# 1_4.net
KiCad netlist of a schematic drawn in Altium Designer
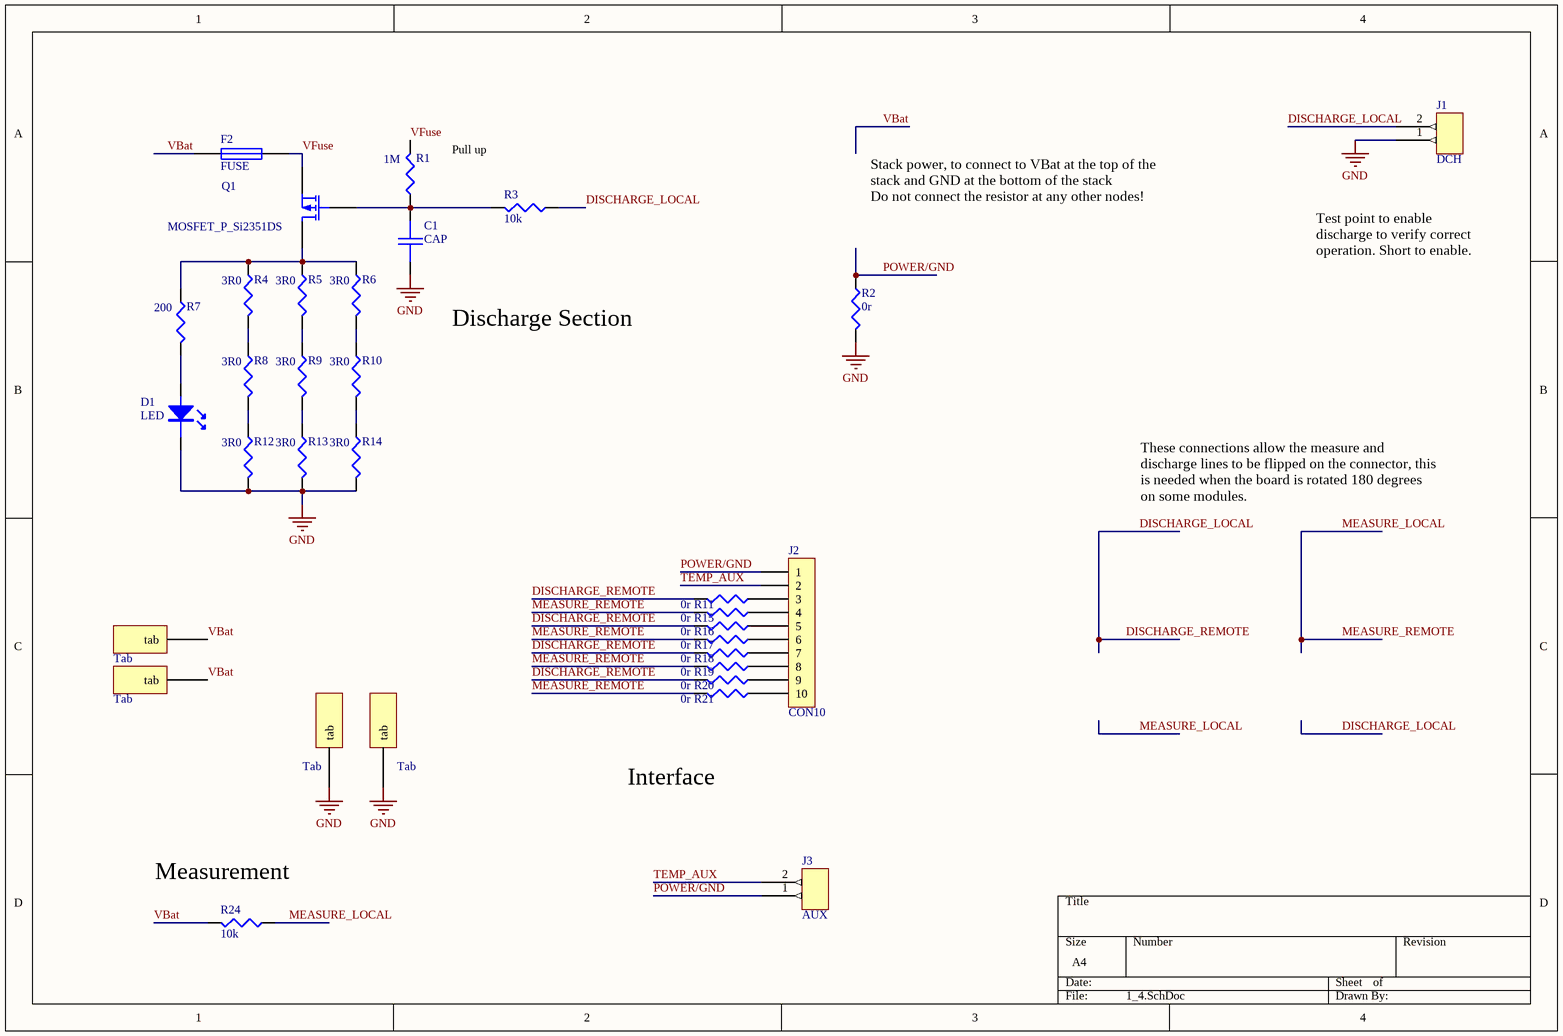
[diagram p0: 1_4.SchDoc]

(export (version "E")
  (design (tool "Eeschema 10.0.6"))
  (components
    (comp (ref "C1")
      (value "CAP")
      (footprint "0603")
      (description "Capacitor")
      (libsource (lib "RCLDQ") (part "CAP"))
    )
    (comp (ref "D1") (value "LED") (footprint "0805LED") (libsource (lib "RCLDQ") (part "LED")))
    (comp (ref "F2")
      (value "FUSE")
      (footprint "LITTELFUSE-154")
      (description "Fuse")
      (libsource (lib "Miscellaneous") (part "FUSE"))
    )
    (comp (ref "J1") (value "DCH") (footprint "IDC2") (libsource (lib "Connectors") (part "CON2")))
    (comp (ref "J2")
      (value "CON10")
      (footprint "IDC10")
      (description "10 pin, right angle, ribbon con with claws")
      (libsource (lib "Connectors") (part "CON10"))
    )
    (comp (ref "J3") (value "AUX") (footprint "IDC2") (libsource (lib "Connectors") (part "CON2")))
    (comp (ref "J4") (value "Tab") (footprint "tab_connect") (libsource (lib "") (part "tab_connection_1")))
    (comp (ref "J5") (value "Tab") (footprint "tab_connect") (libsource (lib "") (part "tab_connection_1")))
    (comp (ref "J6") (value "Tab") (footprint "tab_connect") (libsource (lib "BMS") (part "tab_connection")))
    (comp (ref "J7") (value "Tab") (footprint "tab_connect") (libsource (lib "BMS") (part "tab_connection")))
    (comp (ref "Q1")
      (value "MOSFET_P_Si2351DS")
      (footprint "SOT23-3")
      (description "Si2351DS P-Channel MOSFET")
      (fields (field (name "PUBLISHER") "Altium Limited"))
      (libsource (lib "RCLDQ") (part "MOSFET_P_Si2351DS"))
    )
    (comp (ref "R1")
      (value "~")
      (footprint "0603")
      (description "Resistor")
      (fields (field (name "RESISTANCE") "1M"))
      (libsource (lib "RCLDQ") (part "RES1"))
    )
    (comp (ref "R2")
      (value "~")
      (footprint "1206")
      (description "Resistor")
      (fields (field (name "RESISTANCE") "0r"))
      (libsource (lib "RCLDQ") (part "RES1"))
    )
    (comp (ref "R3")
      (value "~")
      (footprint "0603")
      (description "Resistor")
      (fields (field (name "RESISTANCE") "10k"))
      (libsource (lib "RCLDQ") (part "RES1"))
    )
    (comp (ref "R4")
      (value "3R0")
      (footprint "2512")
      (description "Resistor")
      (libsource (lib "RCLDQ") (part "RES1"))
    )
    (comp (ref "R5")
      (value "3R0")
      (footprint "2512")
      (description "Resistor")
      (libsource (lib "RCLDQ") (part "RES1"))
    )
    (comp (ref "R6")
      (value "3R0")
      (footprint "2512")
      (description "Resistor")
      (libsource (lib "RCLDQ") (part "RES1"))
    )
    (comp (ref "R7")
      (value "200")
      (footprint "0603")
      (description "Resistor")
      (libsource (lib "RCLDQ") (part "RES1"))
    )
    (comp (ref "R8")
      (value "3R0")
      (footprint "2512")
      (description "Resistor")
      (libsource (lib "RCLDQ") (part "RES1"))
    )
    (comp (ref "R9")
      (value "3R0")
      (footprint "2512")
      (description "Resistor")
      (libsource (lib "RCLDQ") (part "RES1"))
    )
    (comp (ref "R10")
      (value "3R0")
      (footprint "2512")
      (description "Resistor")
      (libsource (lib "RCLDQ") (part "RES1"))
    )
    (comp (ref "R11")
      (value "~")
      (footprint "0603")
      (description "Resistor")
      (fields (field (name "RESISTANCE") "0r"))
      (libsource (lib "RCLDQ") (part "RES1"))
    )
    (comp (ref "R12")
      (value "3R0")
      (footprint "2512")
      (description "Resistor")
      (libsource (lib "RCLDQ") (part "RES1"))
    )
    (comp (ref "R13")
      (value "3R0")
      (footprint "2512")
      (description "Resistor")
      (libsource (lib "RCLDQ") (part "RES1"))
    )
    (comp (ref "R14")
      (value "3R0")
      (footprint "2512")
      (description "Resistor")
      (libsource (lib "RCLDQ") (part "RES1"))
    )
    (comp (ref "R15")
      (value "~")
      (footprint "0603")
      (description "Resistor")
      (fields (field (name "RESISTANCE") "0r"))
      (libsource (lib "RCLDQ") (part "RES1"))
    )
    (comp (ref "R16")
      (value "~")
      (footprint "0603")
      (description "Resistor")
      (fields (field (name "RESISTANCE") "0r"))
      (libsource (lib "RCLDQ") (part "RES1"))
    )
    (comp (ref "R17")
      (value "~")
      (footprint "0603")
      (description "Resistor")
      (fields (field (name "RESISTANCE") "0r"))
      (libsource (lib "RCLDQ") (part "RES1"))
    )
    (comp (ref "R18")
      (value "~")
      (footprint "0603")
      (description "Resistor")
      (fields (field (name "RESISTANCE") "0r"))
      (libsource (lib "RCLDQ") (part "RES1"))
    )
    (comp (ref "R19")
      (value "~")
      (footprint "0603")
      (description "Resistor")
      (fields (field (name "RESISTANCE") "0r"))
      (libsource (lib "RCLDQ") (part "RES1"))
    )
    (comp (ref "R20")
      (value "~")
      (footprint "0603")
      (description "Resistor")
      (fields (field (name "RESISTANCE") "0r"))
      (libsource (lib "RCLDQ") (part "RES1"))
    )
    (comp (ref "R21")
      (value "~")
      (footprint "0603")
      (description "Resistor")
      (fields (field (name "RESISTANCE") "0r"))
      (libsource (lib "RCLDQ") (part "RES1"))
    )
    (comp (ref "R24")
      (value "~")
      (footprint "0603")
      (description "Resistor")
      (fields (field (name "RESISTANCE") "10k"))
      (libsource (lib "RCLDQ") (part "RES1"))
    )
  )
  (nets
    (net (code "1") (name "/DISCHARGE_LOCAL") (class "Default")
      (node (ref "J1") (pin "2") (pinfunction "2_2") (pintype "output"))
      (node (ref "R11") (pin "2") (pinfunction "2_2") (pintype "passive"))
      (node (ref "R16") (pin "2") (pinfunction "2_2") (pintype "passive"))
      (node (ref "R18") (pin "2") (pinfunction "2_2") (pintype "passive"))
      (node (ref "R20") (pin "2") (pinfunction "2_2") (pintype "passive"))
      (node (ref "R3") (pin "1") (pinfunction "1_1") (pintype "passive"))
    )
    (net (code "2") (name "/MEASURE_LOCAL") (class "Default")
      (node (ref "R15") (pin "2") (pinfunction "2_2") (pintype "passive"))
      (node (ref "R17") (pin "2") (pinfunction "2_2") (pintype "passive"))
      (node (ref "R19") (pin "2") (pinfunction "2_2") (pintype "passive"))
      (node (ref "R21") (pin "2") (pinfunction "2_2") (pintype "passive"))
      (node (ref "R24") (pin "1") (pinfunction "1_1") (pintype "passive"))
    )
    (net (code "3") (name "/POWER{slash}GND") (class "Default")
      (node (ref "J2") (pin "1") (pinfunction "1_1") (pintype "passive"))
      (node (ref "J3") (pin "1") (pinfunction "1_1") (pintype "output"))
      (node (ref "R2") (pin "1") (pinfunction "1_1") (pintype "passive"))
    )
    (net (code "4") (name "/TEMP_AUX") (class "Default")
      (node (ref "J2") (pin "2") (pinfunction "2_2") (pintype "passive"))
      (node (ref "J3") (pin "2") (pinfunction "2_2") (pintype "output"))
    )
    (net (code "5") (name "/VBat") (class "Default")
      (node (ref "F2") (pin "1") (pinfunction "1_1") (pintype "passive"))
      (node (ref "J4") (pin "0") (pinfunction "tab_0") (pintype "passive"))
      (node (ref "J5") (pin "0") (pinfunction "tab_0") (pintype "passive"))
      (node (ref "R24") (pin "2") (pinfunction "2_2") (pintype "passive"))
    )
    (net (code "6") (name "/VFuse") (class "Default")
      (node (ref "F2") (pin "2") (pinfunction "2_2") (pintype "passive"))
      (node (ref "Q1") (pin "2") (pinfunction "S_2") (pintype "passive"))
      (node (ref "R1") (pin "2") (pinfunction "2_2") (pintype "passive"))
    )
    (net (code "7") (name "GND") (class "Default")
      (node (ref "C1") (pin "2") (pinfunction "2_2") (pintype "passive"))
      (node (ref "D1") (pin "K") (pinfunction "K_K") (pintype "passive"))
      (node (ref "J1") (pin "1") (pinfunction "1_1") (pintype "output"))
      (node (ref "J6") (pin "0") (pinfunction "tab_0") (pintype "passive"))
      (node (ref "J7") (pin "0") (pinfunction "tab_0") (pintype "passive"))
      (node (ref "R12") (pin "2") (pinfunction "2_2") (pintype "passive"))
      (node (ref "R13") (pin "2") (pinfunction "2_2") (pintype "passive"))
      (node (ref "R14") (pin "2") (pinfunction "2_2") (pintype "passive"))
      (node (ref "R2") (pin "2") (pinfunction "2_2") (pintype "passive"))
    )
    (net (code "8") (name "Net-(D1-PadA)") (class "Default")
      (node (ref "D1") (pin "A") (pinfunction "A_A") (pintype "passive"))
      (node (ref "R7") (pin "2") (pinfunction "2_2") (pintype "passive"))
    )
    (net (code "9") (name "Net-(J2-Pad3)") (class "Default")
      (node (ref "J2") (pin "3") (pinfunction "3_3") (pintype "passive"))
      (node (ref "R11") (pin "1") (pinfunction "1_1") (pintype "passive"))
    )
    (net (code "10") (name "Net-(J2-Pad4)") (class "Default")
      (node (ref "J2") (pin "4") (pinfunction "4_4") (pintype "passive"))
      (node (ref "R15") (pin "1") (pinfunction "1_1") (pintype "passive"))
    )
    (net (code "11") (name "Net-(J2-Pad5)") (class "Default")
      (node (ref "J2") (pin "5") (pinfunction "5_5") (pintype "passive"))
      (node (ref "R16") (pin "1") (pinfunction "1_1") (pintype "passive"))
    )
    (net (code "12") (name "Net-(J2-Pad6)") (class "Default")
      (node (ref "J2") (pin "6") (pinfunction "6_6") (pintype "passive"))
      (node (ref "R17") (pin "1") (pinfunction "1_1") (pintype "passive"))
    )
    (net (code "13") (name "Net-(J2-Pad7)") (class "Default")
      (node (ref "J2") (pin "7") (pinfunction "7_7") (pintype "passive"))
      (node (ref "R18") (pin "1") (pinfunction "1_1") (pintype "passive"))
    )
    (net (code "14") (name "Net-(J2-Pad8)") (class "Default")
      (node (ref "J2") (pin "8") (pinfunction "8_8") (pintype "passive"))
      (node (ref "R19") (pin "1") (pinfunction "1_1") (pintype "passive"))
    )
    (net (code "15") (name "Net-(J2-Pad9)") (class "Default")
      (node (ref "J2") (pin "9") (pinfunction "9_9") (pintype "passive"))
      (node (ref "R20") (pin "1") (pinfunction "1_1") (pintype "passive"))
    )
    (net (code "16") (name "Net-(J2-Pad10)") (class "Default")
      (node (ref "J2") (pin "10") (pinfunction "10_10") (pintype "passive"))
      (node (ref "R21") (pin "1") (pinfunction "1_1") (pintype "passive"))
    )
    (net (code "17") (name "Net-(Q1-D)") (class "Default")
      (node (ref "Q1") (pin "3") (pinfunction "D_3") (pintype "passive"))
      (node (ref "R4") (pin "1") (pinfunction "1_1") (pintype "passive"))
      (node (ref "R5") (pin "1") (pinfunction "1_1") (pintype "passive"))
      (node (ref "R6") (pin "1") (pinfunction "1_1") (pintype "passive"))
      (node (ref "R7") (pin "1") (pinfunction "1_1") (pintype "passive"))
    )
    (net (code "18") (name "Net-(Q1-G)") (class "Default")
      (node (ref "C1") (pin "1") (pinfunction "1_1") (pintype "passive"))
      (node (ref "Q1") (pin "1") (pinfunction "G_1") (pintype "passive"))
      (node (ref "R1") (pin "1") (pinfunction "1_1") (pintype "passive"))
      (node (ref "R3") (pin "2") (pinfunction "2_2") (pintype "passive"))
    )
    (net (code "19") (name "Net-(R4-Pad2)") (class "Default")
      (node (ref "R4") (pin "2") (pinfunction "2_2") (pintype "passive"))
      (node (ref "R8") (pin "1") (pinfunction "1_1") (pintype "passive"))
    )
    (net (code "20") (name "Net-(R5-Pad2)") (class "Default")
      (node (ref "R5") (pin "2") (pinfunction "2_2") (pintype "passive"))
      (node (ref "R9") (pin "1") (pinfunction "1_1") (pintype "passive"))
    )
    (net (code "21") (name "Net-(R10-Pad1)") (class "Default")
      (node (ref "R10") (pin "1") (pinfunction "1_1") (pintype "passive"))
      (node (ref "R6") (pin "2") (pinfunction "2_2") (pintype "passive"))
    )
    (net (code "22") (name "Net-(R10-Pad2)") (class "Default")
      (node (ref "R10") (pin "2") (pinfunction "2_2") (pintype "passive"))
      (node (ref "R14") (pin "1") (pinfunction "1_1") (pintype "passive"))
    )
    (net (code "23") (name "Net-(R12-Pad1)") (class "Default")
      (node (ref "R12") (pin "1") (pinfunction "1_1") (pintype "passive"))
      (node (ref "R8") (pin "2") (pinfunction "2_2") (pintype "passive"))
    )
    (net (code "24") (name "Net-(R13-Pad1)") (class "Default")
      (node (ref "R13") (pin "1") (pinfunction "1_1") (pintype "passive"))
      (node (ref "R9") (pin "2") (pinfunction "2_2") (pintype "passive"))
    )
  )
)
